# smh.net
KiCad netlist of a schematic drawn in EAGLE
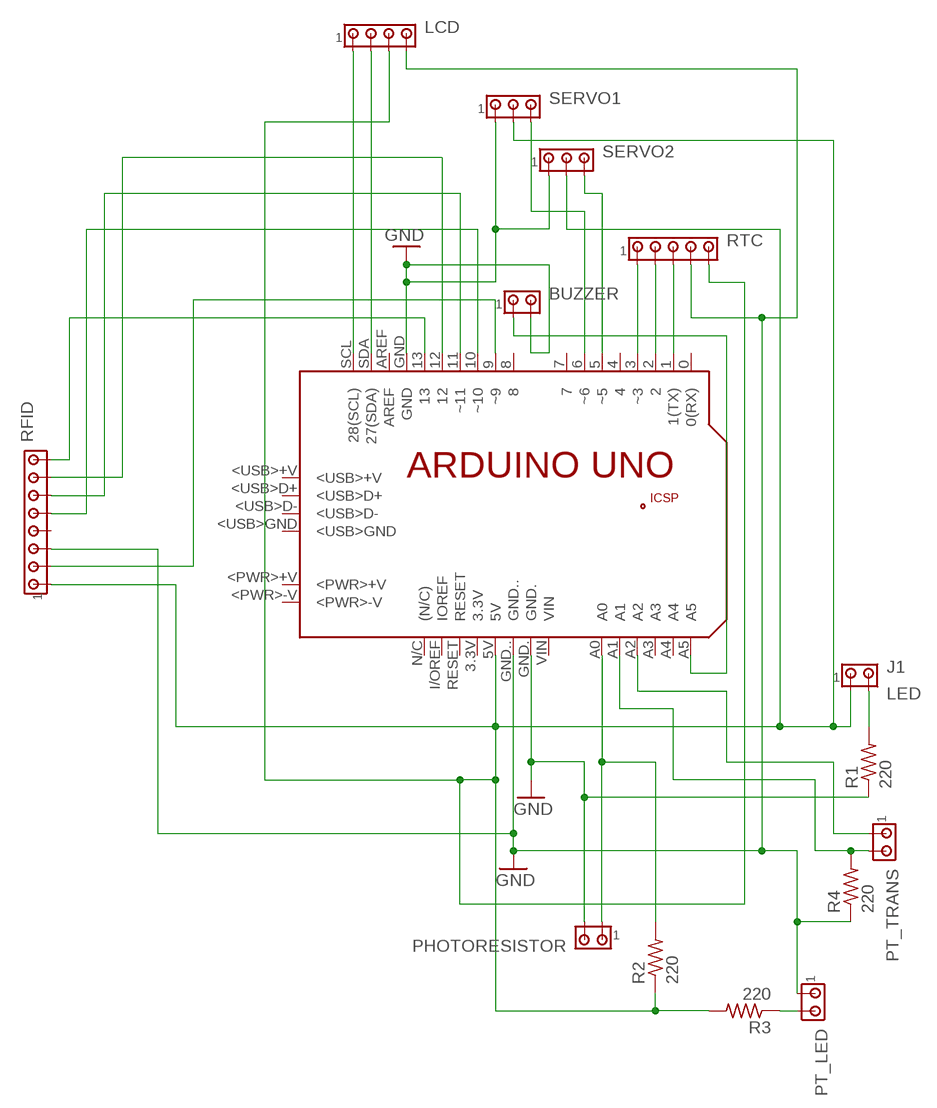
[diagram p0: schematic, sheet 1]

(export (version "E")
  (design (tool "Eeschema 10.0.6"))
  (components
    (comp (ref "BUZZER")
      (value "MTA02-100")
      (footprint "eagle-import:10X02MTA")
      (libsource (lib "eagle-import") (part "MTA02-100"))
    )
    (comp (ref "J1")
      (value "LED")
      (footprint "eagle-import:10X02MTA")
      (libsource (lib "eagle-import") (part "MTA02-100"))
    )
    (comp (ref "LCD")
      (value "MTA04-100")
      (footprint "eagle-import:10X04MTA")
      (libsource (lib "eagle-import") (part "MTA04-100"))
    )
    (comp (ref "PCB1")
      (value "ARDUINO_UNO")
      (footprint "eagle-import:ARDUINO_UNO")
      (libsource (lib "eagle-import") (part "ARDUINO_UNO"))
    )
    (comp (ref "PHOTORESISTOR")
      (value "MTA02-100")
      (footprint "eagle-import:10X02MTA")
      (libsource (lib "eagle-import") (part "MTA02-100"))
    )
    (comp (ref "PT_LED")
      (value "MTA02-100")
      (footprint "eagle-import:10X02MTA")
      (libsource (lib "eagle-import") (part "MTA02-100"))
    )
    (comp (ref "PT_TRANS")
      (value "MTA02-100")
      (footprint "eagle-import:10X02MTA")
      (libsource (lib "eagle-import") (part "MTA02-100"))
    )
    (comp (ref "R1")
      (value "220")
      (footprint "eagle-import:0309_10")
      (libsource (lib "eagle-import") (part "R-US_0309/10"))
    )
    (comp (ref "R2")
      (value "220")
      (footprint "eagle-import:0309_10")
      (libsource (lib "eagle-import") (part "R-US_0309/10"))
    )
    (comp (ref "R3")
      (value "220")
      (footprint "eagle-import:0309_10")
      (libsource (lib "eagle-import") (part "R-US_0309/10"))
    )
    (comp (ref "R4")
      (value "220")
      (footprint "eagle-import:0309_10")
      (libsource (lib "eagle-import") (part "R-US_0309/10"))
    )
    (comp (ref "RFID")
      (value "MTA08-100")
      (footprint "eagle-import:10X08MTA")
      (libsource (lib "eagle-import") (part "MTA08-100"))
    )
    (comp (ref "RTC")
      (value "MTA05-100")
      (footprint "eagle-import:10X05MTA")
      (libsource (lib "eagle-import") (part "MTA05-100"))
    )
    (comp (ref "SERVO1")
      (value "MTA03-100")
      (footprint "eagle-import:10X03MTA")
      (libsource (lib "eagle-import") (part "MTA03-100"))
    )
    (comp (ref "SERVO2")
      (value "MTA03-100")
      (footprint "eagle-import:10X03MTA")
      (libsource (lib "eagle-import") (part "MTA03-100"))
    )
  )
  (nets
    (net (code "1") (name "GND") (class "Default")
      (node (ref "BUZZER") (pin "2") (pinfunction "2_2") (pintype "passive"))
      (node (ref "LCD") (pin "4") (pinfunction "4_4") (pintype "passive"))
      (node (ref "PCB1") (pin "GND") (pinfunction "GND_GND") (pintype "bidirectional"))
      (node (ref "PCB1") (pin "GND.") (pinfunction "GND._GND.") (pintype "bidirectional"))
      (node (ref "PCB1") (pin "GND..") (pinfunction "GND.._GND..") (pintype "bidirectional"))
      (node (ref "PHOTORESISTOR") (pin "2") (pinfunction "2_2") (pintype "passive"))
      (node (ref "PT_LED") (pin "1") (pinfunction "1_1") (pintype "passive"))
      (node (ref "R1") (pin "1") (pinfunction "1_1") (pintype "passive"))
      (node (ref "R4") (pin "1") (pinfunction "1_1") (pintype "passive"))
      (node (ref "RFID") (pin "3") (pinfunction "3_3") (pintype "passive"))
      (node (ref "RTC") (pin "4") (pinfunction "4_4") (pintype "passive"))
      (node (ref "SERVO1") (pin "1") (pinfunction "1_1") (pintype "passive"))
      (node (ref "SERVO2") (pin "1") (pinfunction "1_1") (pintype "passive"))
    )
    (net (code "2") (name "Net-(BUZZER-Pad1)") (class "Default")
      (node (ref "BUZZER") (pin "1") (pinfunction "1_1") (pintype "passive"))
      (node (ref "PCB1") (pin "A5") (pinfunction "A5_A5") (pintype "bidirectional"))
    )
    (net (code "3") (name "Net-(J1-Pad1)") (class "Default")
      (node (ref "J1") (pin "1") (pinfunction "1_1") (pintype "passive"))
      (node (ref "LCD") (pin "3") (pinfunction "3_3") (pintype "passive"))
      (node (ref "PCB1") (pin "5V") (pinfunction "5V_5V") (pintype "bidirectional"))
      (node (ref "R2") (pin "1") (pinfunction "1_1") (pintype "passive"))
      (node (ref "R3") (pin "2") (pinfunction "2_2") (pintype "passive"))
      (node (ref "RFID") (pin "1") (pinfunction "1_1") (pintype "passive"))
      (node (ref "RTC") (pin "5") (pinfunction "5_5") (pintype "passive"))
      (node (ref "SERVO1") (pin "2") (pinfunction "2_2") (pintype "passive"))
      (node (ref "SERVO2") (pin "2") (pinfunction "2_2") (pintype "passive"))
    )
    (net (code "4") (name "Net-(J1-Pad2)") (class "Default")
      (node (ref "J1") (pin "2") (pinfunction "2_2") (pintype "passive"))
      (node (ref "R1") (pin "2") (pinfunction "2_2") (pintype "passive"))
    )
    (net (code "5") (name "Net-(PCB1-1(TX))") (class "Default")
      (node (ref "PCB1") (pin "1") (pinfunction "1(TX)_1") (pintype "bidirectional"))
      (node (ref "RTC") (pin "3") (pinfunction "3_3") (pintype "passive"))
    )
    (net (code "6") (name "Net-(PCB1-27(SDA))") (class "Default")
      (node (ref "LCD") (pin "2") (pinfunction "2_2") (pintype "passive"))
      (node (ref "PCB1") (pin "SDA") (pinfunction "27(SDA)_SDA") (pintype "bidirectional"))
    )
    (net (code "7") (name "Net-(PCB1-28(SCL))") (class "Default")
      (node (ref "LCD") (pin "1") (pinfunction "1_1") (pintype "passive"))
      (node (ref "PCB1") (pin "SCL") (pinfunction "28(SCL)_SCL") (pintype "bidirectional"))
    )
    (net (code "8") (name "Net-(PCB1-Pad2)") (class "Default")
      (node (ref "PCB1") (pin "2") (pinfunction "2_2") (pintype "bidirectional"))
      (node (ref "RTC") (pin "2") (pinfunction "2_2") (pintype "passive"))
    )
    (net (code "9") (name "Net-(PCB1-Pad12)") (class "Default")
      (node (ref "PCB1") (pin "12") (pinfunction "12_12") (pintype "bidirectional"))
      (node (ref "RFID") (pin "7") (pinfunction "7_7") (pintype "passive"))
    )
    (net (code "10") (name "Net-(PCB1-Pad13)") (class "Default")
      (node (ref "PCB1") (pin "13") (pinfunction "13_13") (pintype "bidirectional"))
      (node (ref "RFID") (pin "8") (pinfunction "8_8") (pintype "passive"))
    )
    (net (code "11") (name "Net-(PCB1-PadA0)") (class "Default")
      (node (ref "PCB1") (pin "A0") (pinfunction "A0_A0") (pintype "bidirectional"))
      (node (ref "PHOTORESISTOR") (pin "1") (pinfunction "1_1") (pintype "passive"))
      (node (ref "R2") (pin "2") (pinfunction "2_2") (pintype "passive"))
    )
    (net (code "12") (name "Net-(PCB1-PadA1)") (class "Default")
      (node (ref "PCB1") (pin "A1") (pinfunction "A1_A1") (pintype "bidirectional"))
      (node (ref "PT_TRANS") (pin "2") (pinfunction "2_2") (pintype "passive"))
      (node (ref "R4") (pin "2") (pinfunction "2_2") (pintype "passive"))
    )
    (net (code "13") (name "Net-(PCB1-PadA2)") (class "Default")
      (node (ref "PCB1") (pin "A2") (pinfunction "A2_A2") (pintype "bidirectional"))
      (node (ref "PT_TRANS") (pin "1") (pinfunction "1_1") (pintype "passive"))
    )
    (net (code "14") (name "Net-(PCB1-~{3})") (class "Default")
      (node (ref "PCB1") (pin "3") (pinfunction "~{3}_3") (pintype "bidirectional"))
      (node (ref "RTC") (pin "1") (pinfunction "1_1") (pintype "passive"))
    )
    (net (code "15") (name "Net-(PCB1-~{5})") (class "Default")
      (node (ref "PCB1") (pin "5") (pinfunction "~{5}_5") (pintype "bidirectional"))
      (node (ref "SERVO2") (pin "3") (pinfunction "3_3") (pintype "passive"))
    )
    (net (code "16") (name "Net-(PCB1-~{6})") (class "Default")
      (node (ref "PCB1") (pin "6") (pinfunction "~{6}_6") (pintype "bidirectional"))
      (node (ref "SERVO1") (pin "3") (pinfunction "3_3") (pintype "passive"))
    )
    (net (code "17") (name "Net-(PCB1-~{9})") (class "Default")
      (node (ref "PCB1") (pin "9") (pinfunction "~{9}_9") (pintype "bidirectional"))
      (node (ref "RFID") (pin "2") (pinfunction "2_2") (pintype "passive"))
    )
    (net (code "18") (name "Net-(PCB1-~{10})") (class "Default")
      (node (ref "PCB1") (pin "10") (pinfunction "~{10}_10") (pintype "bidirectional"))
      (node (ref "RFID") (pin "5") (pinfunction "5_5") (pintype "passive"))
    )
    (net (code "19") (name "Net-(PCB1-~{11})") (class "Default")
      (node (ref "PCB1") (pin "11") (pinfunction "~{11}_11") (pintype "bidirectional"))
      (node (ref "RFID") (pin "6") (pinfunction "6_6") (pintype "passive"))
    )
    (net (code "20") (name "Net-(PT_LED-Pad2)") (class "Default")
      (node (ref "PT_LED") (pin "2") (pinfunction "2_2") (pintype "passive"))
      (node (ref "R3") (pin "1") (pinfunction "1_1") (pintype "passive"))
    )
    (net (code "21") (name "unconnected-(PCB1-(N{slash}C)-PadN{slash}C)") (class "Default")
      (node (ref "PCB1") (pin "N/C") (pinfunction "(N/C)_N/C") (pintype "bidirectional"))
    )
    (net (code "22") (name "unconnected-(PCB1-0(RX)-Pad0)") (class "Default")
      (node (ref "PCB1") (pin "0") (pinfunction "0(RX)_0") (pintype "bidirectional"))
    )
    (net (code "23") (name "unconnected-(PCB1-IOREF-PadI{slash}OREF)") (class "Default")
      (node (ref "PCB1") (pin "I/OREF") (pinfunction "IOREF_I/OREF") (pintype "bidirectional"))
    )
    (net (code "24") (name "unconnected-(PCB1-Pad+5V)") (class "Default")
      (node (ref "PCB1") (pin "+5V") (pinfunction "+5V_+5V") (pintype "bidirectional"))
    )
    (net (code "25") (name "unconnected-(PCB1-Pad3.3V)") (class "Default")
      (node (ref "PCB1") (pin "3.3V") (pinfunction "3.3V_3.3V") (pintype "bidirectional"))
    )
    (net (code "26") (name "unconnected-(PCB1-Pad4)") (class "Default")
      (node (ref "PCB1") (pin "4") (pinfunction "4_4") (pintype "bidirectional"))
    )
    (net (code "27") (name "unconnected-(PCB1-Pad7)") (class "Default")
      (node (ref "PCB1") (pin "7") (pinfunction "7_7") (pintype "bidirectional"))
    )
    (net (code "28") (name "unconnected-(PCB1-Pad8)") (class "Default")
      (node (ref "PCB1") (pin "8") (pinfunction "8_8") (pintype "bidirectional"))
    )
    (net (code "29") (name "unconnected-(PCB1-Pad<PWR>+V)") (class "Default")
      (node (ref "PCB1") (pin "<PWR>+V") (pinfunction "<PWR>+V_<PWR>+V") (pintype "bidirectional"))
    )
    (net (code "30") (name "unconnected-(PCB1-Pad<PWR>-V)") (class "Default")
      (node (ref "PCB1") (pin "<PWR>-V") (pinfunction "<PWR>-V_<PWR>-V") (pintype "bidirectional"))
    )
    (net (code "31") (name "unconnected-(PCB1-Pad<USB>+V)") (class "Default")
      (node (ref "PCB1") (pin "<USB>+V") (pinfunction "<USB>+V_<USB>+V") (pintype "bidirectional"))
    )
    (net (code "32") (name "unconnected-(PCB1-Pad<USB>D+)") (class "Default")
      (node (ref "PCB1") (pin "<USB>D+") (pinfunction "<USB>D+_<USB>D+") (pintype "bidirectional"))
    )
    (net (code "33") (name "unconnected-(PCB1-Pad<USB>D-)") (class "Default")
      (node (ref "PCB1") (pin "<USB>D-") (pinfunction "<USB>D-_<USB>D-") (pintype "bidirectional"))
    )
    (net (code "34") (name "unconnected-(PCB1-Pad<USB>GND)") (class "Default")
      (node (ref "PCB1") (pin "<USB>GND") (pinfunction "<USB>GND_<USB>GND") (pintype "bidirectional"))
    )
    (net (code "35") (name "unconnected-(PCB1-PadA3)") (class "Default")
      (node (ref "PCB1") (pin "A3") (pinfunction "A3_A3") (pintype "bidirectional"))
    )
    (net (code "36") (name "unconnected-(PCB1-PadA4)") (class "Default")
      (node (ref "PCB1") (pin "A4") (pinfunction "A4_A4") (pintype "bidirectional"))
    )
    (net (code "37") (name "unconnected-(PCB1-PadAREF)") (class "Default")
      (node (ref "PCB1") (pin "AREF") (pinfunction "AREF_AREF") (pintype "bidirectional"))
    )
    (net (code "38") (name "unconnected-(PCB1-PadGND_)") (class "Default")
      (node (ref "PCB1") (pin "GND_") (pinfunction "GND__GND_") (pintype "bidirectional"))
    )
    (net (code "39") (name "unconnected-(PCB1-PadMISO)") (class "Default")
      (node (ref "PCB1") (pin "MISO") (pinfunction "MISO_MISO") (pintype "bidirectional"))
    )
    (net (code "40") (name "unconnected-(PCB1-PadMOSI)") (class "Default")
      (node (ref "PCB1") (pin "MOSI") (pinfunction "MOSI_MOSI") (pintype "bidirectional"))
    )
    (net (code "41") (name "unconnected-(PCB1-PadRESET)") (class "Default")
      (node (ref "PCB1") (pin "RESET") (pinfunction "RESET_RESET") (pintype "bidirectional"))
    )
    (net (code "42") (name "unconnected-(PCB1-PadRESET.)") (class "Default")
      (node (ref "PCB1") (pin "RESET.") (pinfunction "RESET._RESET.") (pintype "bidirectional"))
    )
    (net (code "43") (name "unconnected-(PCB1-PadSCK)") (class "Default")
      (node (ref "PCB1") (pin "SCK") (pinfunction "SCK_SCK") (pintype "bidirectional"))
    )
    (net (code "44") (name "unconnected-(PCB1-PadVIN)") (class "Default")
      (node (ref "PCB1") (pin "VIN") (pinfunction "VIN_VIN") (pintype "bidirectional"))
    )
    (net (code "45") (name "unconnected-(RFID-Pad4)") (class "Default")
      (node (ref "RFID") (pin "4") (pinfunction "4_4") (pintype "passive"))
    )
  )
)
